# 6_channel_esp32_energy_meter.net
KiCad netlist of a schematic drawn in EAGLE
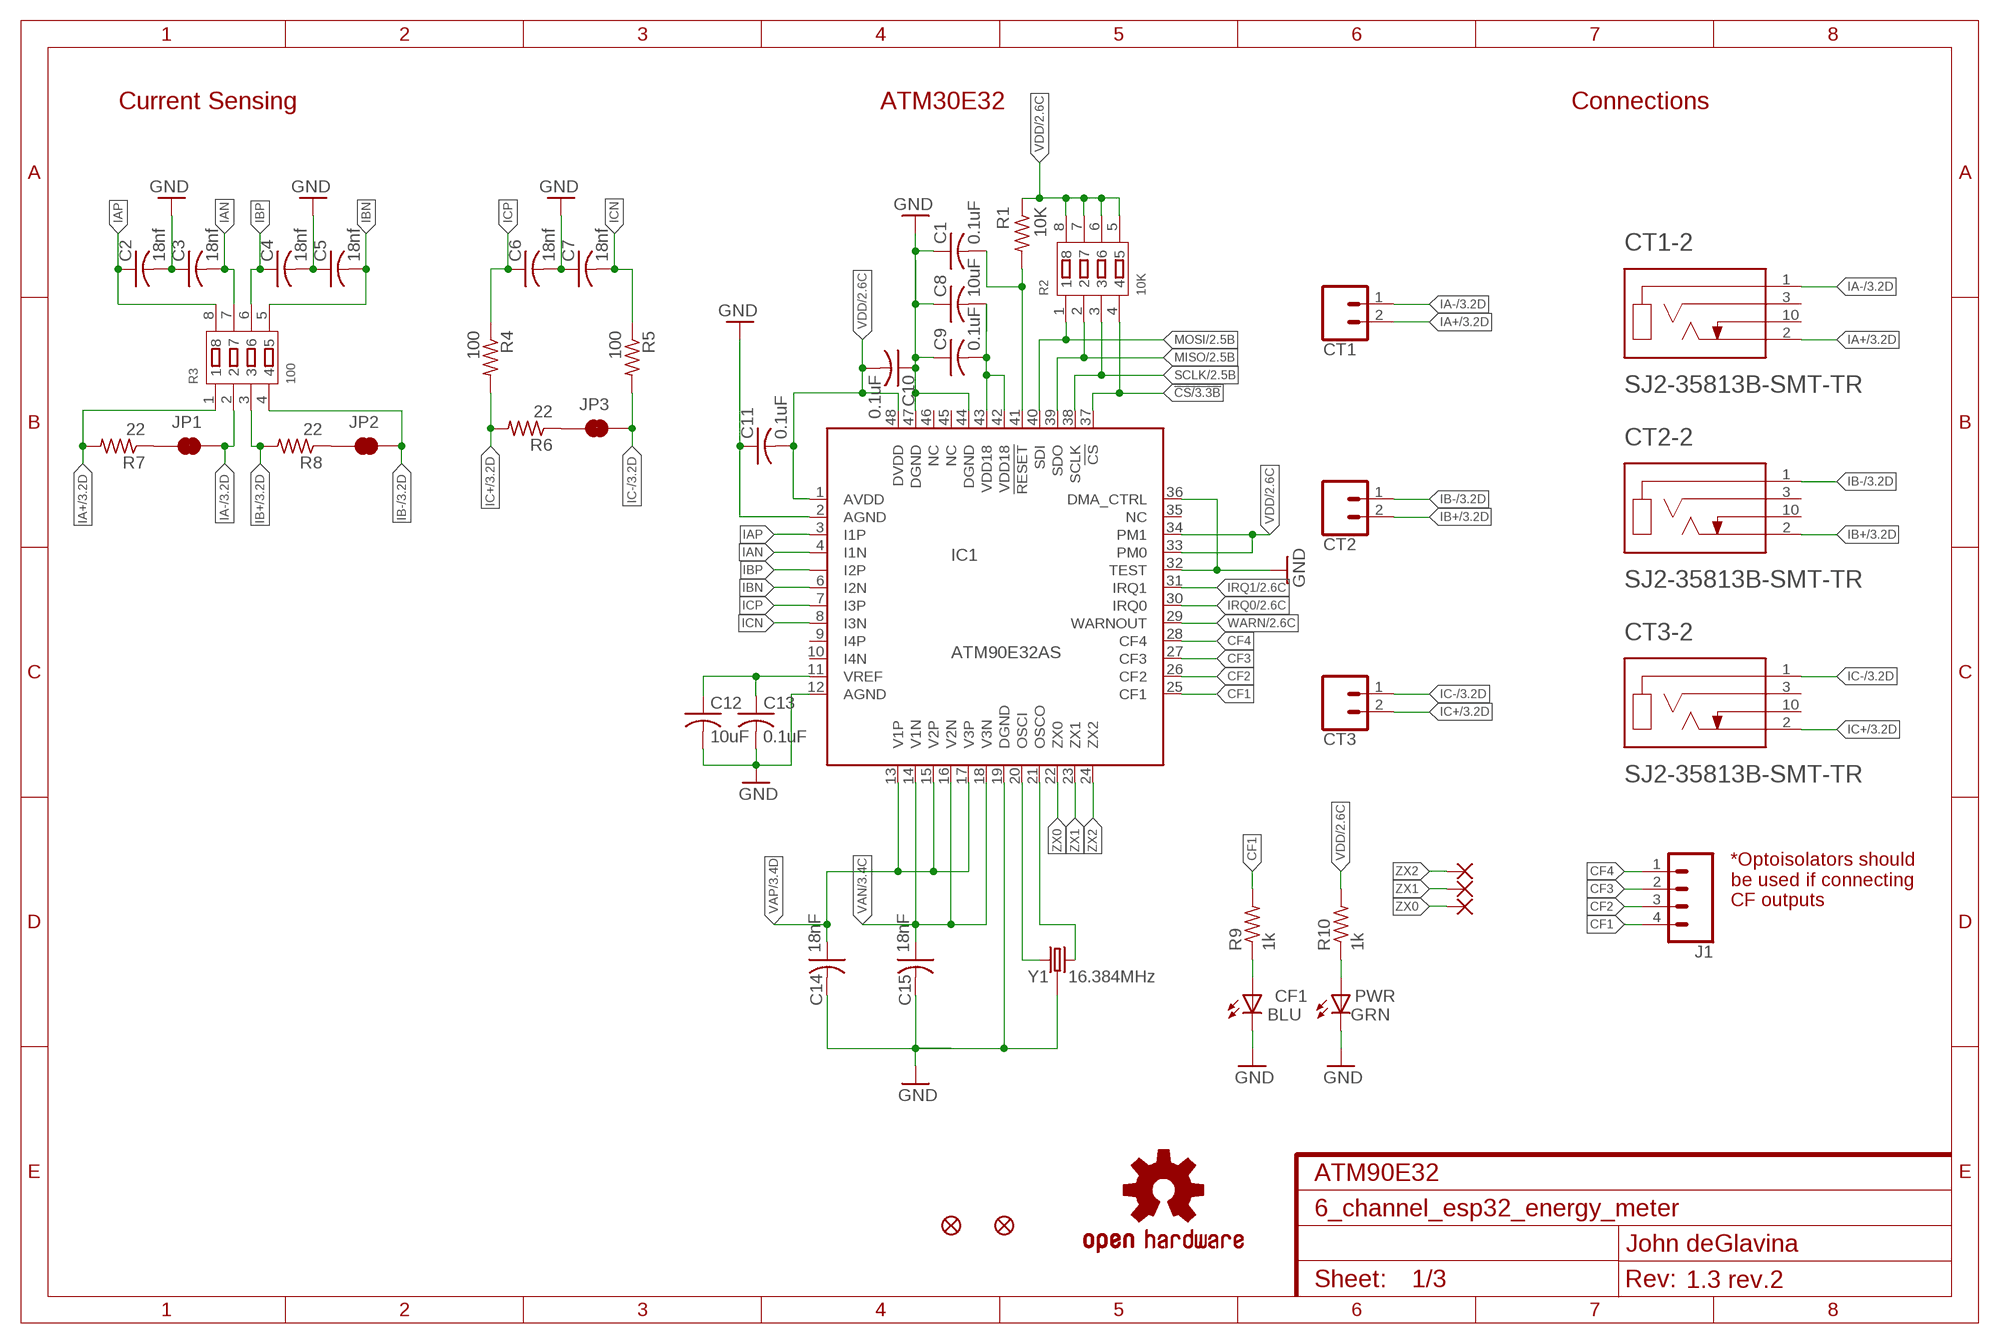
[diagram p0: schematic, sheet 1]
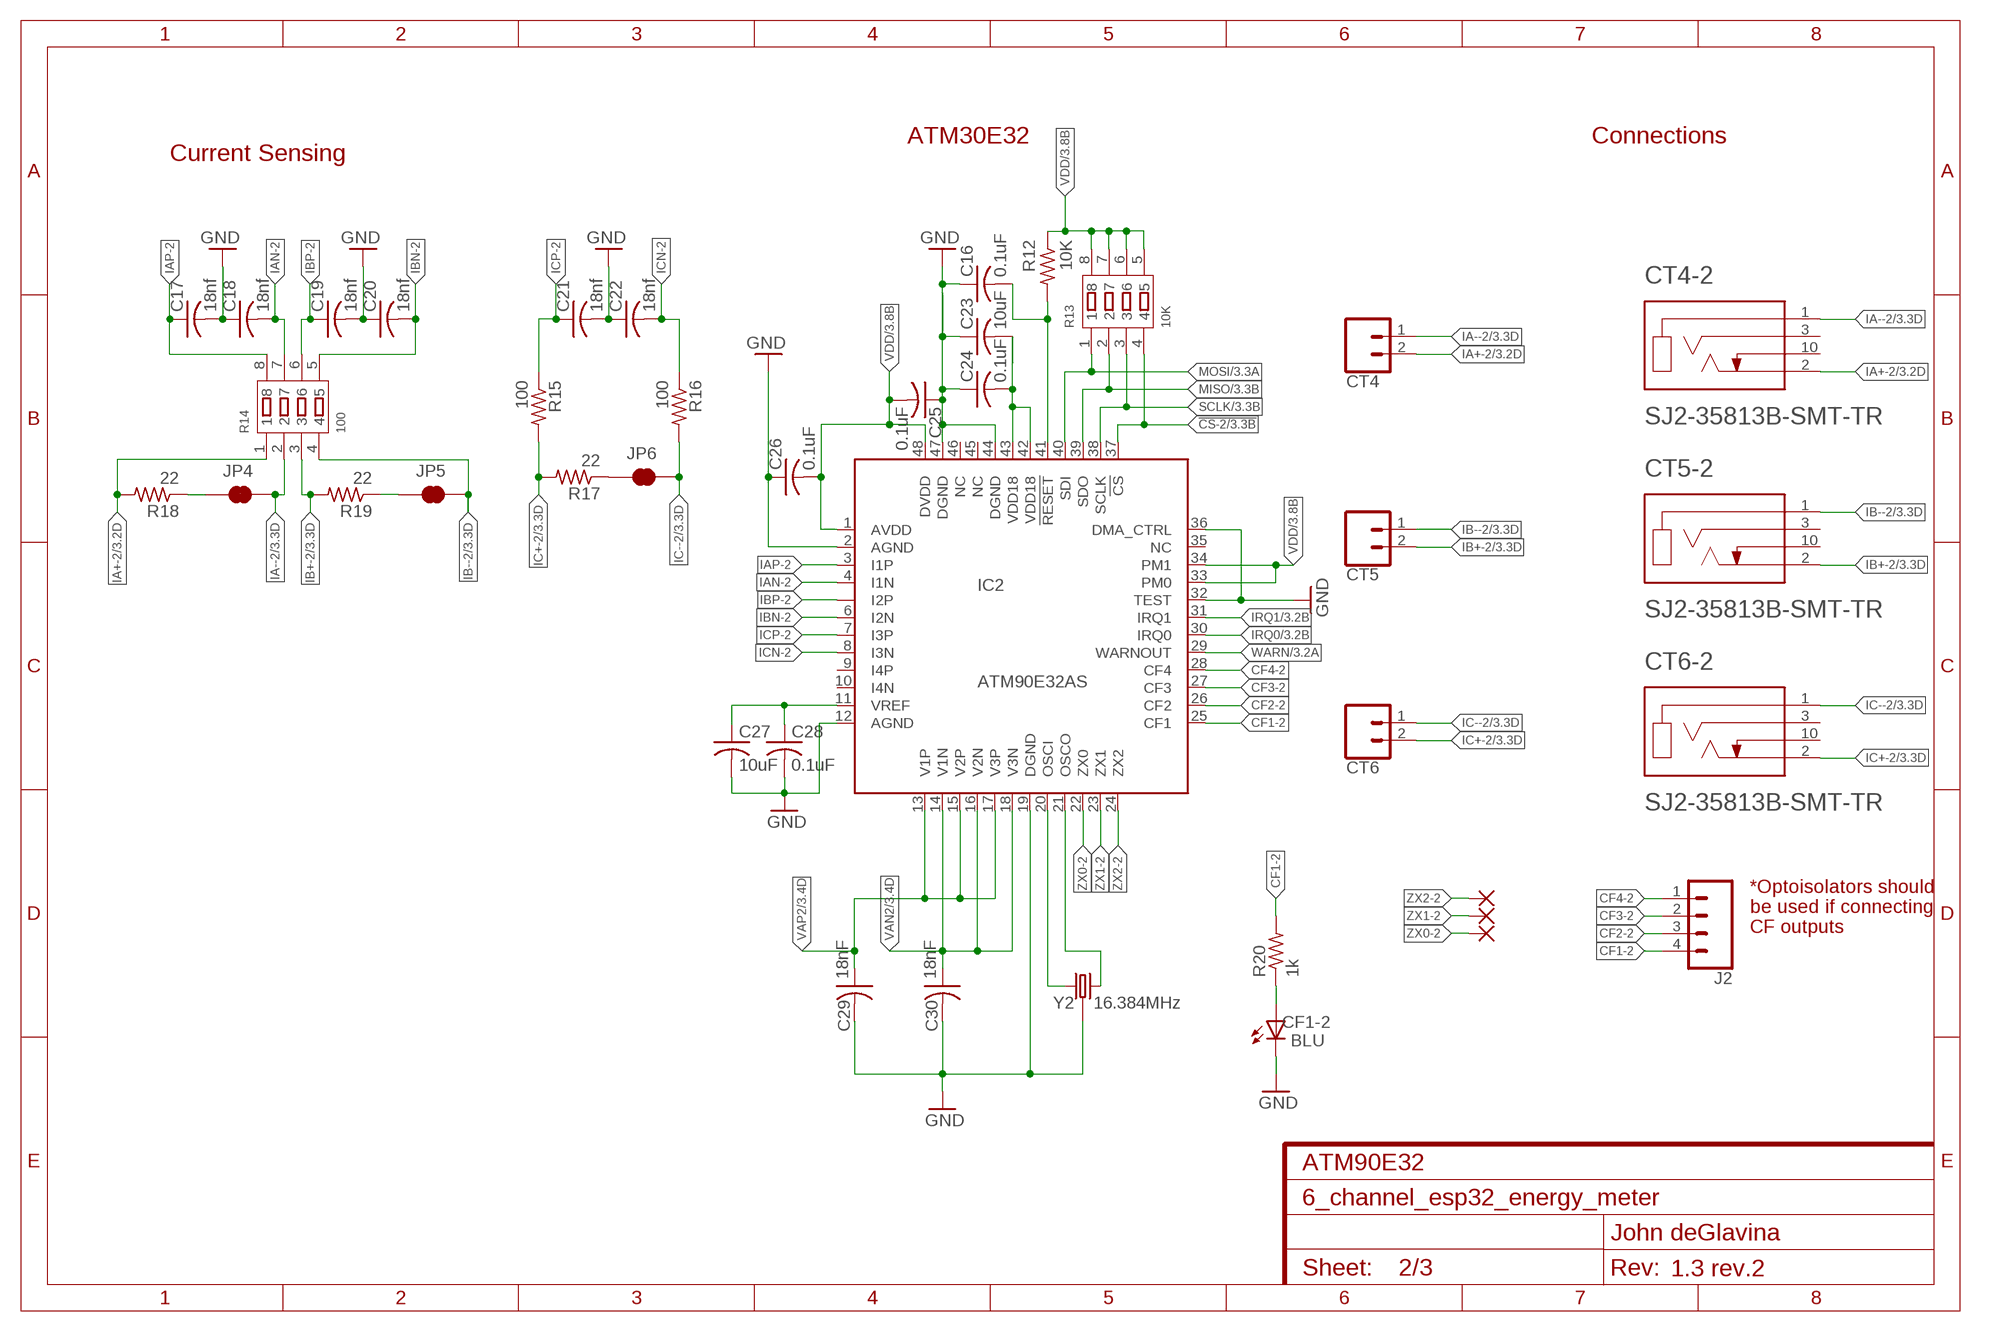
[diagram p1: schematic, sheet 2]
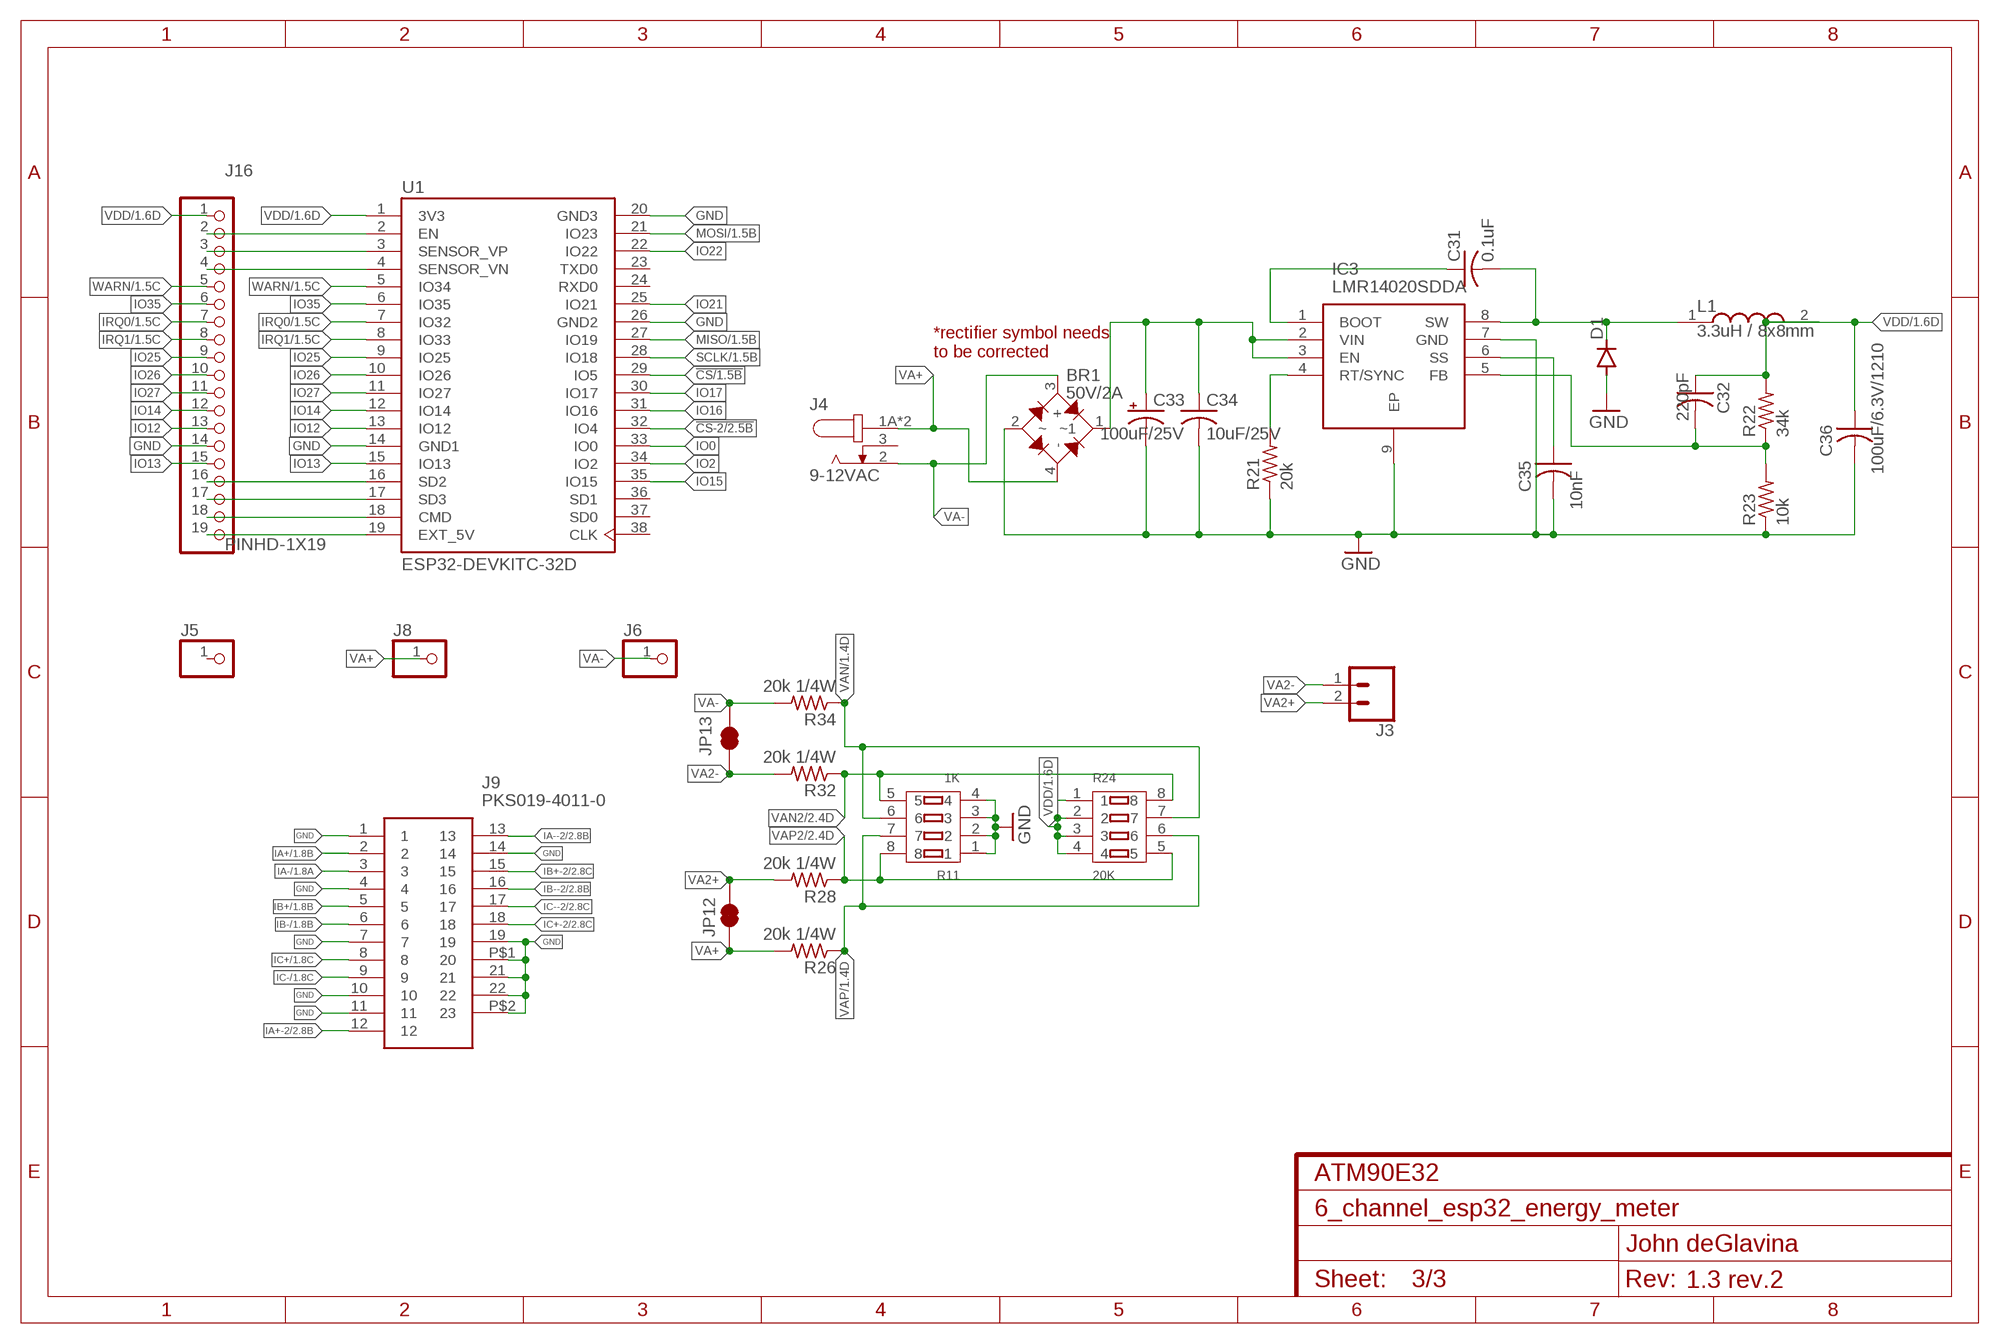
[diagram p2: schematic, sheet 3]

(export (version "E")
  (design (tool "Eeschema 10.0.6"))
  (components
    (comp (ref "BR1")
      (value "50V/2A")
      (footprint "eagle-import:SOP270P700X270-4")
      (fields
        (field (name "MANUFACTURER_PART_NUMBER") "CDBHM240L-HF")
        (field (name "MOUSER_PART_NUMBER") "750-CDBHM240L-HF")
        (field (name "RS_PART_NUMBER") "9066719")
      )
      (libsource (lib "eagle-import") (part "CDBHM240L-HF"))
    )
    (comp (ref "C31")
      (value "0.1uF")
      (footprint "eagle-import:C0603")
      (libsource (lib "eagle-import") (part "C-USC0603"))
    )
    (comp (ref "C32")
      (value "220pF")
      (footprint "eagle-import:C0603")
      (libsource (lib "eagle-import") (part "C-USC0603"))
    )
    (comp (ref "C33")
      (value "100uF/25V")
      (footprint "eagle-import:UD-6,3X7,7_NICHICON")
      (libsource (lib "eagle-import") (part "CPOL-USUD-6,3X7,7"))
    )
    (comp (ref "C34")
      (value "10uF/25V")
      (footprint "eagle-import:C0805")
      (libsource (lib "eagle-import") (part "C-USC0805"))
    )
    (comp (ref "C35")
      (value "10nF")
      (footprint "eagle-import:C0603")
      (libsource (lib "eagle-import") (part "C-USC0603"))
    )
    (comp (ref "C36")
      (value "100uF/6.3V/1210")
      (footprint "eagle-import:C1210")
      (libsource (lib "eagle-import") (part "C-USC1210"))
    )
    (comp (ref "D1")
      (value "DIODE-DO214AC")
      (footprint "eagle-import:DO214AC")
      (libsource (lib "eagle-import") (part "DIODE-DO214AC"))
    )
    (comp (ref "IC3")
      (value "LMR14020SDDA")
      (footprint "eagle-import:SOIC127P600X170-9N")
      (fields
        (field (name "MOUSER_PART_NUMBER") "595-LMR14020SDDA")
        (field (name "RS_PART_NUMBER") "1629813")
      )
      (libsource (lib "eagle-import") (part "LMR14020SDDA"))
    )
    (comp (ref "J3")
      (value "CONN_023.5MM")
      (footprint "eagle-import:SCREWTERMINAL-3.5MM-2")
      (libsource (lib "eagle-import") (part "CONN_023.5MM"))
    )
    (comp (ref "J4")
      (value "9-12VAC")
      (footprint "eagle-import:CUI_PJ-002AH-SMT-TR")
      (fields (field (name "MF") "CUI") (field (name "MP") "PJ-002AH-SMT-TR"))
      (libsource (lib "eagle-import") (part "PJ-002AH-SMT-TR"))
    )
    (comp (ref "J5")
      (value "PINHD1X1-SM1X01_SM")
      (footprint "eagle-import:1X01-SM")
      (libsource (lib "eagle-import") (part "PINHD1X1-SM1X01_SM"))
    )
    (comp (ref "J6")
      (value "PINHD1X1-SM1X01_SM")
      (footprint "eagle-import:1X01-SM")
      (libsource (lib "eagle-import") (part "PINHD1X1-SM1X01_SM"))
    )
    (comp (ref "J8")
      (value "PINHD1X1-SM1X01_SM")
      (footprint "eagle-import:1X01-SM")
      (libsource (lib "eagle-import") (part "PINHD1X1-SM1X01_SM"))
    )
    (comp (ref "J9")
      (value "PKS019-4011-0")
      (footprint "eagle-import:PKS01940110")
      (fields (field (name "MOUSER_PART_NUMBER") "945-PKS019-4011-0"))
      (libsource (lib "eagle-import") (part "PKS019-4011-0"))
    )
    (comp (ref "J16")
      (value "PINHD-1X19")
      (footprint "eagle-import:1X19")
      (fields (field (name "SPICEPREFIX") "X"))
      (libsource (lib "eagle-import") (part "PINHD-1X19"))
    )
    (comp (ref "JP12")
      (value "JUMPER-SMT_2_NC_TRACE_SILK")
      (footprint "eagle-import:SMT-JUMPER_2_NC_TRACE_SILK")
      (libsource (lib "eagle-import") (part "JUMPER-SMT_2_NC_TRACE_SILK"))
    )
    (comp (ref "JP13")
      (value "JUMPER-SMT_2_NC_TRACE_SILK")
      (footprint "eagle-import:SMT-JUMPER_2_NC_TRACE_SILK")
      (libsource (lib "eagle-import") (part "JUMPER-SMT_2_NC_TRACE_SILK"))
    )
    (comp (ref "L1")
      (value "3.3uH / 8x8mm")
      (footprint "eagle-import:INDPM8082X300N")
      (fields (field (name "MANUFACTURER_PART_NUMBER") "1273AS-H-3R3N=P3"))
      (libsource (lib "eagle-import") (part "1273AS-H-3R3N=P3"))
    )
    (comp (ref "R11")
      (value "1K")
      (footprint "eagle-import:RA1206-8")
      (fields (field (name "MPN") "Chip-Array-Series-1%"))
      (libsource (lib "eagle-import") (part "SMD-RES-ARRAY-1K-4R(RA1206-8)"))
    )
    (comp (ref "R21")
      (value "20k")
      (footprint "eagle-import:R0603")
      (libsource (lib "eagle-import") (part "R-US_R0603"))
    )
    (comp (ref "R22")
      (value "34k")
      (footprint "eagle-import:R0603")
      (libsource (lib "eagle-import") (part "R-US_R0603"))
    )
    (comp (ref "R23")
      (value "10k")
      (footprint "eagle-import:R0603")
      (libsource (lib "eagle-import") (part "R-US_R0603"))
    )
    (comp (ref "R24")
      (value "20K")
      (footprint "eagle-import:RA1206-8")
      (fields (field (name "MPN") "Chip-Array-Series-1%"))
      (libsource (lib "eagle-import") (part "SMD-RES-ARRAY-1K-4R(RA1206-8)"))
    )
    (comp (ref "R26")
      (value "20k 1/4W")
      (footprint "eagle-import:R0603")
      (libsource (lib "eagle-import") (part "R-US_R0603"))
    )
    (comp (ref "R28")
      (value "20k 1/4W")
      (footprint "eagle-import:R0603")
      (libsource (lib "eagle-import") (part "R-US_R0603"))
    )
    (comp (ref "R32")
      (value "20k 1/4W")
      (footprint "eagle-import:R0603")
      (libsource (lib "eagle-import") (part "R-US_R0603"))
    )
    (comp (ref "R34")
      (value "20k 1/4W")
      (footprint "eagle-import:R0603")
      (libsource (lib "eagle-import") (part "R-US_R0603"))
    )
    (comp (ref "U1")
      (value "ESP32-DEVKITC-32D")
      (footprint "eagle-import:MODULE_ESP32-DEVKITC-32D")
      (fields (field (name "MF") "Espressif Systems"))
      (libsource (lib "eagle-import") (part "ESP32-DEVKITC-32D"))
    )
    (comp (ref "C16")
      (value "0.1uF")
      (footprint "eagle-import:C0603")
      (libsource (lib "eagle-import") (part "C-USC0603"))
    )
    (comp (ref "C17")
      (value "18nf")
      (footprint "eagle-import:C0603")
      (libsource (lib "eagle-import") (part "C-USC0603"))
    )
    (comp (ref "C18")
      (value "18nf")
      (footprint "eagle-import:C0603")
      (libsource (lib "eagle-import") (part "C-USC0603"))
    )
    (comp (ref "C19")
      (value "18nf")
      (footprint "eagle-import:C0603")
      (libsource (lib "eagle-import") (part "C-USC0603"))
    )
    (comp (ref "C20")
      (value "18nf")
      (footprint "eagle-import:C0603")
      (libsource (lib "eagle-import") (part "C-USC0603"))
    )
    (comp (ref "C21")
      (value "18nf")
      (footprint "eagle-import:C0603")
      (libsource (lib "eagle-import") (part "C-USC0603"))
    )
    (comp (ref "C22")
      (value "18nf")
      (footprint "eagle-import:C0603")
      (libsource (lib "eagle-import") (part "C-USC0603"))
    )
    (comp (ref "C23")
      (value "10uF")
      (footprint "eagle-import:C0603")
      (libsource (lib "eagle-import") (part "C-USC0603"))
    )
    (comp (ref "C24")
      (value "0.1uF")
      (footprint "eagle-import:C0603")
      (libsource (lib "eagle-import") (part "C-USC0603"))
    )
    (comp (ref "C25")
      (value "0.1uF")
      (footprint "eagle-import:C0603")
      (libsource (lib "eagle-import") (part "C-USC0603"))
    )
    (comp (ref "C26")
      (value "0.1uF")
      (footprint "eagle-import:C0603")
      (libsource (lib "eagle-import") (part "C-USC0603"))
    )
    (comp (ref "C27")
      (value "10uF")
      (footprint "eagle-import:C0603")
      (libsource (lib "eagle-import") (part "C-USC0603"))
    )
    (comp (ref "C28")
      (value "0.1uF")
      (footprint "eagle-import:C0603")
      (libsource (lib "eagle-import") (part "C-USC0603"))
    )
    (comp (ref "C29")
      (value "18nF")
      (footprint "eagle-import:C0603")
      (libsource (lib "eagle-import") (part "C-USC0603"))
    )
    (comp (ref "C30")
      (value "18nF")
      (footprint "eagle-import:C0603")
      (libsource (lib "eagle-import") (part "C-USC0603"))
    )
    (comp (ref "CF1-2")
      (value "BLU")
      (footprint "eagle-import:CHIPLED_0603")
      (libsource (lib "eagle-import") (part "LEDCHIPLED_0603"))
    )
    (comp (ref "CT4")
      (value "CONN_023.5MM")
      (footprint "eagle-import:SCREWTERMINAL-3.5MM-2")
      (libsource (lib "eagle-import") (part "SparkFun-Connectors_8231346_CONN_023.5MM"))
    )
    (comp (ref "CT4-2")
      (value "SJ2-35813B-SMT-TR")
      (footprint "eagle-import:CUI_SJ2-35813B-SMT-TR")
      (fields (field (name "MANUFACTURER") "CUI"))
      (libsource (lib "eagle-import") (part "SJ2-35813B-SMT-TR"))
    )
    (comp (ref "CT5")
      (value "CONN_023.5MM")
      (footprint "eagle-import:SCREWTERMINAL-3.5MM-2")
      (libsource (lib "eagle-import") (part "SparkFun-Connectors_8231346_CONN_023.5MM"))
    )
    (comp (ref "CT5-2")
      (value "SJ2-35813B-SMT-TR")
      (footprint "eagle-import:CUI_SJ2-35813B-SMT-TR")
      (fields (field (name "MANUFACTURER") "CUI"))
      (libsource (lib "eagle-import") (part "SJ2-35813B-SMT-TR"))
    )
    (comp (ref "CT6")
      (value "CONN_023.5MM")
      (footprint "eagle-import:SCREWTERMINAL-3.5MM-2")
      (libsource (lib "eagle-import") (part "SparkFun-Connectors_8231346_CONN_023.5MM"))
    )
    (comp (ref "CT6-2")
      (value "SJ2-35813B-SMT-TR")
      (footprint "eagle-import:CUI_SJ2-35813B-SMT-TR")
      (fields (field (name "MANUFACTURER") "CUI"))
      (libsource (lib "eagle-import") (part "SJ2-35813B-SMT-TR"))
    )
    (comp (ref "IC2")
      (value "ATM90E32AS")
      (footprint "eagle-import:QFP50P900X900X120-48")
      (fields (field (name "SPICEPREFIX") "X"))
      (libsource (lib "eagle-import") (part "ATM90E36"))
    )
    (comp (ref "J2")
      (value "CONN_04")
      (footprint "eagle-import:1X04")
      (libsource (lib "eagle-import") (part "CONN_04"))
    )
    (comp (ref "JP4")
      (value "JUMPER-SMT_2_NC_TRACE_SILK")
      (footprint "eagle-import:SMT-JUMPER_2_NC_TRACE_SILK")
      (libsource (lib "eagle-import") (part "JUMPER-SMT_2_NC_TRACE_SILK"))
    )
    (comp (ref "JP5")
      (value "JUMPER-SMT_2_NC_TRACE_SILK")
      (footprint "eagle-import:SMT-JUMPER_2_NC_TRACE_SILK")
      (libsource (lib "eagle-import") (part "JUMPER-SMT_2_NC_TRACE_SILK"))
    )
    (comp (ref "JP6")
      (value "JUMPER-SMT_2_NC_TRACE_SILK")
      (footprint "eagle-import:SMT-JUMPER_2_NC_TRACE_SILK")
      (libsource (lib "eagle-import") (part "JUMPER-SMT_2_NC_TRACE_SILK"))
    )
    (comp (ref "R12")
      (value "10K")
      (footprint "eagle-import:R0603")
      (libsource (lib "eagle-import") (part "R-US_R0603"))
    )
    (comp (ref "R13")
      (value "10K")
      (footprint "eagle-import:RA1206-8")
      (fields (field (name "MPN") "Chip-Array-Series-1%"))
      (libsource (lib "eagle-import") (part "SMD-RES-ARRAY-1K-4R(RA1206-8)"))
    )
    (comp (ref "R14")
      (value "100")
      (footprint "eagle-import:RA1206-8")
      (fields (field (name "MPN") "Chip-Array-Series-1%"))
      (libsource (lib "eagle-import") (part "SMD-RES-ARRAY-1K-4R(RA1206-8)"))
    )
    (comp (ref "R15")
      (value "100")
      (footprint "eagle-import:R0603")
      (libsource (lib "eagle-import") (part "R-US_R0603"))
    )
    (comp (ref "R16")
      (value "100")
      (footprint "eagle-import:R0603")
      (libsource (lib "eagle-import") (part "R-US_R0603"))
    )
    (comp (ref "R17")
      (value "22")
      (footprint "eagle-import:R0603")
      (libsource (lib "eagle-import") (part "R-US_R0603"))
    )
    (comp (ref "R18")
      (value "22")
      (footprint "eagle-import:R0603")
      (libsource (lib "eagle-import") (part "R-US_R0603"))
    )
    (comp (ref "R19")
      (value "22")
      (footprint "eagle-import:R0603")
      (libsource (lib "eagle-import") (part "R-US_R0603"))
    )
    (comp (ref "R20")
      (value "1k")
      (footprint "eagle-import:R0603")
      (libsource (lib "eagle-import") (part "R-US_R0603"))
    )
    (comp (ref "Y2")
      (value "16.384MHz")
      (footprint "eagle-import:CRYSTAL-SMD-3.2X2.5MM")
      (libsource (lib "eagle-import") (part "CRYSTAL-GROUNDEDSMD-3.2X2.5"))
    )
    (comp (ref "ZX0-2")
      (value "WIREPADSMD1,27-254")
      (footprint "eagle-import:SMD1,27-2,54")
      (libsource (lib "eagle-import") (part "WIREPADSMD1,27-254"))
    )
    (comp (ref "ZX1-2")
      (value "WIREPADSMD1,27-254")
      (footprint "eagle-import:SMD1,27-2,54")
      (libsource (lib "eagle-import") (part "WIREPADSMD1,27-254"))
    )
    (comp (ref "ZX2-2")
      (value "WIREPADSMD1,27-254")
      (footprint "eagle-import:SMD1,27-2,54")
      (libsource (lib "eagle-import") (part "WIREPADSMD1,27-254"))
    )
    (comp (ref "C1")
      (value "0.1uF")
      (footprint "eagle-import:C0603")
      (libsource (lib "eagle-import") (part "C-USC0603"))
    )
    (comp (ref "C2")
      (value "18nf")
      (footprint "eagle-import:C0603")
      (libsource (lib "eagle-import") (part "C-USC0603"))
    )
    (comp (ref "C3")
      (value "18nf")
      (footprint "eagle-import:C0603")
      (libsource (lib "eagle-import") (part "C-USC0603"))
    )
    (comp (ref "C4")
      (value "18nf")
      (footprint "eagle-import:C0603")
      (libsource (lib "eagle-import") (part "C-USC0603"))
    )
    (comp (ref "C5")
      (value "18nf")
      (footprint "eagle-import:C0603")
      (libsource (lib "eagle-import") (part "C-USC0603"))
    )
    (comp (ref "C6")
      (value "18nf")
      (footprint "eagle-import:C0603")
      (libsource (lib "eagle-import") (part "C-USC0603"))
    )
    (comp (ref "C7")
      (value "18nf")
      (footprint "eagle-import:C0603")
      (libsource (lib "eagle-import") (part "C-USC0603"))
    )
    (comp (ref "C8")
      (value "10uF")
      (footprint "eagle-import:C0603")
      (libsource (lib "eagle-import") (part "C-USC0603"))
    )
    (comp (ref "C9")
      (value "0.1uF")
      (footprint "eagle-import:C0603")
      (libsource (lib "eagle-import") (part "C-USC0603"))
    )
    (comp (ref "C10")
      (value "0.1uF")
      (footprint "eagle-import:C0603")
      (libsource (lib "eagle-import") (part "C-USC0603"))
    )
    (comp (ref "C11")
      (value "0.1uF")
      (footprint "eagle-import:C0603")
      (libsource (lib "eagle-import") (part "C-USC0603"))
    )
    (comp (ref "C12")
      (value "10uF")
      (footprint "eagle-import:C0603")
      (libsource (lib "eagle-import") (part "C-USC0603"))
    )
    (comp (ref "C13")
      (value "0.1uF")
      (footprint "eagle-import:C0603")
      (libsource (lib "eagle-import") (part "C-USC0603"))
    )
    (comp (ref "C14")
      (value "18nF")
      (footprint "eagle-import:C0603")
      (libsource (lib "eagle-import") (part "C-USC0603"))
    )
    (comp (ref "C15")
      (value "18nF")
      (footprint "eagle-import:C0603")
      (libsource (lib "eagle-import") (part "C-USC0603"))
    )
    (comp (ref "CF1")
      (value "BLU")
      (footprint "eagle-import:CHIPLED_0603")
      (libsource (lib "eagle-import") (part "LEDCHIPLED_0603"))
    )
    (comp (ref "CT1")
      (value "CONN_023.5MM")
      (footprint "eagle-import:SCREWTERMINAL-3.5MM-2")
      (libsource (lib "eagle-import") (part "SparkFun-Connectors_8231346_CONN_023.5MM"))
    )
    (comp (ref "CT1-2")
      (value "SJ2-35813B-SMT-TR")
      (footprint "eagle-import:CUI_SJ2-35813B-SMT-TR")
      (fields (field (name "MANUFACTURER") "CUI"))
      (libsource (lib "eagle-import") (part "SJ2-35813B-SMT-TR"))
    )
    (comp (ref "CT2")
      (value "CONN_023.5MM")
      (footprint "eagle-import:SCREWTERMINAL-3.5MM-2")
      (libsource (lib "eagle-import") (part "SparkFun-Connectors_8231346_CONN_023.5MM"))
    )
    (comp (ref "CT2-2")
      (value "SJ2-35813B-SMT-TR")
      (footprint "eagle-import:CUI_SJ2-35813B-SMT-TR")
      (fields (field (name "MANUFACTURER") "CUI"))
      (libsource (lib "eagle-import") (part "SJ2-35813B-SMT-TR"))
    )
    (comp (ref "CT3")
      (value "CONN_023.5MM")
      (footprint "eagle-import:SCREWTERMINAL-3.5MM-2")
      (libsource (lib "eagle-import") (part "SparkFun-Connectors_8231346_CONN_023.5MM"))
    )
    (comp (ref "CT3-2")
      (value "SJ2-35813B-SMT-TR")
      (footprint "eagle-import:CUI_SJ2-35813B-SMT-TR")
      (fields (field (name "MANUFACTURER") "CUI"))
      (libsource (lib "eagle-import") (part "SJ2-35813B-SMT-TR"))
    )
    (comp (ref "FD1")
      (value "FIDUCIALUFIDUCIAL")
      (footprint "eagle-import:FIDUCIAL-MICRO")
      (libsource (lib "eagle-import") (part "FIDUCIALUFIDUCIAL"))
    )
    (comp (ref "FD2")
      (value "FIDUCIALUFIDUCIAL")
      (footprint "eagle-import:FIDUCIAL-MICRO")
      (libsource (lib "eagle-import") (part "FIDUCIALUFIDUCIAL"))
    )
    (comp (ref "IC1")
      (value "ATM90E32AS")
      (footprint "eagle-import:QFP50P900X900X120-48")
      (fields (field (name "SPICEPREFIX") "X"))
      (libsource (lib "eagle-import") (part "ATM90E36"))
    )
    (comp (ref "J1")
      (value "CONN_04")
      (footprint "eagle-import:1X04")
      (libsource (lib "eagle-import") (part "CONN_04"))
    )
    (comp (ref "JP1")
      (value "JUMPER-SMT_2_NC_TRACE_SILK")
      (footprint "eagle-import:SMT-JUMPER_2_NC_TRACE_SILK")
      (libsource (lib "eagle-import") (part "JUMPER-SMT_2_NC_TRACE_SILK"))
    )
    (comp (ref "JP2")
      (value "JUMPER-SMT_2_NC_TRACE_SILK")
      (footprint "eagle-import:SMT-JUMPER_2_NC_TRACE_SILK")
      (libsource (lib "eagle-import") (part "JUMPER-SMT_2_NC_TRACE_SILK"))
    )
    (comp (ref "JP3")
      (value "JUMPER-SMT_2_NC_TRACE_SILK")
      (footprint "eagle-import:SMT-JUMPER_2_NC_TRACE_SILK")
      (libsource (lib "eagle-import") (part "JUMPER-SMT_2_NC_TRACE_SILK"))
    )
    (comp (ref "LOGO1")
      (value "OSHW-LOGOS")
      (footprint "eagle-import:OSHW-LOGO-S")
      (libsource (lib "eagle-import") (part "OSHW-LOGOS"))
    )
    (comp (ref "PWR")
      (value "GRN")
      (footprint "eagle-import:CHIPLED_0603")
      (libsource (lib "eagle-import") (part "LEDCHIPLED_0603"))
    )
    (comp (ref "R1")
      (value "10K")
      (footprint "eagle-import:R0603")
      (libsource (lib "eagle-import") (part "R-US_R0603"))
    )
    (comp (ref "R2")
      (value "10K")
      (footprint "eagle-import:RA1206-8")
      (fields (field (name "MPN") "Chip-Array-Series-1%"))
      (libsource (lib "eagle-import") (part "SMD-RES-ARRAY-1K-4R(RA1206-8)"))
    )
    (comp (ref "R3")
      (value "100")
      (footprint "eagle-import:RA1206-8")
      (fields (field (name "MPN") "Chip-Array-Series-1%"))
      (libsource (lib "eagle-import") (part "SMD-RES-ARRAY-1K-4R(RA1206-8)"))
    )
    (comp (ref "R4")
      (value "100")
      (footprint "eagle-import:R0603")
      (libsource (lib "eagle-import") (part "R-US_R0603"))
    )
    (comp (ref "R5")
      (value "100")
      (footprint "eagle-import:R0603")
      (libsource (lib "eagle-import") (part "R-US_R0603"))
    )
    (comp (ref "R6")
      (value "22")
      (footprint "eagle-import:R0603")
      (libsource (lib "eagle-import") (part "R-US_R0603"))
    )
    (comp (ref "R7")
      (value "22")
      (footprint "eagle-import:R0603")
      (libsource (lib "eagle-import") (part "R-US_R0603"))
    )
    (comp (ref "R8")
      (value "22")
      (footprint "eagle-import:R0603")
      (libsource (lib "eagle-import") (part "R-US_R0603"))
    )
    (comp (ref "R9")
      (value "1k")
      (footprint "eagle-import:R0603")
      (libsource (lib "eagle-import") (part "R-US_R0603"))
    )
    (comp (ref "R10")
      (value "1k")
      (footprint "eagle-import:R0603")
      (libsource (lib "eagle-import") (part "R-US_R0603"))
    )
    (comp (ref "Y1")
      (value "16.384MHz")
      (footprint "eagle-import:CRYSTAL-SMD-3.2X2.5MM")
      (libsource (lib "eagle-import") (part "CRYSTAL-GROUNDEDSMD-3.2X2.5"))
    )
    (comp (ref "ZX0")
      (value "WIREPADSMD1,27-254")
      (footprint "eagle-import:SMD1,27-2,54")
      (libsource (lib "eagle-import") (part "WIREPADSMD1,27-254"))
    )
    (comp (ref "ZX1")
      (value "WIREPADSMD1,27-254")
      (footprint "eagle-import:SMD1,27-2,54")
      (libsource (lib "eagle-import") (part "WIREPADSMD1,27-254"))
    )
    (comp (ref "ZX2")
      (value "WIREPADSMD1,27-254")
      (footprint "eagle-import:SMD1,27-2,54")
      (libsource (lib "eagle-import") (part "WIREPADSMD1,27-254"))
    )
  )
  (nets
    (net (code "1") (name "CF1") (class "Default")
      (node (ref "IC1") (pin "25") (pinfunction "CF1_25") (pintype "output"))
      (node (ref "J1") (pin "4") (pinfunction "4_4") (pintype "passive"))
      (node (ref "R9") (pin "2") (pinfunction "2_2") (pintype "passive"))
    )
    (net (code "2") (name "CF1-2") (class "Default")
      (node (ref "IC2") (pin "25") (pinfunction "CF1_25") (pintype "output"))
      (node (ref "J2") (pin "4") (pinfunction "4_4") (pintype "passive"))
      (node (ref "R20") (pin "2") (pinfunction "2_2") (pintype "passive"))
    )
    (net (code "3") (name "CF2") (class "Default")
      (node (ref "IC1") (pin "26") (pinfunction "CF2_26") (pintype "output"))
      (node (ref "J1") (pin "3") (pinfunction "3_3") (pintype "passive"))
    )
    (net (code "4") (name "CF2-2") (class "Default")
      (node (ref "IC2") (pin "26") (pinfunction "CF2_26") (pintype "output"))
      (node (ref "J2") (pin "3") (pinfunction "3_3") (pintype "passive"))
    )
    (net (code "5") (name "CF3") (class "Default")
      (node (ref "IC1") (pin "27") (pinfunction "CF3_27") (pintype "output"))
      (node (ref "J1") (pin "2") (pinfunction "2_2") (pintype "passive"))
    )
    (net (code "6") (name "CF3-2") (class "Default")
      (node (ref "IC2") (pin "27") (pinfunction "CF3_27") (pintype "output"))
      (node (ref "J2") (pin "2") (pinfunction "2_2") (pintype "passive"))
    )
    (net (code "7") (name "CF4") (class "Default")
      (node (ref "IC1") (pin "28") (pinfunction "CF4_28") (pintype "output"))
      (node (ref "J1") (pin "1") (pinfunction "1_1") (pintype "passive"))
    )
    (net (code "8") (name "CF4-2") (class "Default")
      (node (ref "IC2") (pin "28") (pinfunction "CF4_28") (pintype "output"))
      (node (ref "J2") (pin "1") (pinfunction "1_1") (pintype "passive"))
    )
    (net (code "9") (name "GND") (class "Default")
      (node (ref "BR1") (pin "2") (pinfunction "~_2") (pintype "bidirectional"))
      (node (ref "C1") (pin "1") (pinfunction "1_1") (pintype "passive"))
      (node (ref "C10") (pin "1") (pinfunction "1_1") (pintype "passive"))
      (node (ref "C11") (pin "1") (pinfunction "1_1") (pintype "passive"))
      (node (ref "C12") (pin "2") (pinfunction "2_2") (pintype "passive"))
      (node (ref "C13") (pin "2") (pinfunction "2_2") (pintype "passive"))
      (node (ref "C14") (pin "2") (pinfunction "2_2") (pintype "passive"))
      (node (ref "C15") (pin "2") (pinfunction "2_2") (pintype "passive"))
      (node (ref "C16") (pin "1") (pinfunction "1_1") (pintype "passive"))
      (node (ref "C17") (pin "2") (pinfunction "2_2") (pintype "passive"))
      (node (ref "C18") (pin "1") (pinfunction "1_1") (pintype "passive"))
      (node (ref "C19") (pin "2") (pinfunction "2_2") (pintype "passive"))
      (node (ref "C2") (pin "2") (pinfunction "2_2") (pintype "passive"))
      (node (ref "C20") (pin "1") (pinfunction "1_1") (pintype "passive"))
      (node (ref "C21") (pin "2") (pinfunction "2_2") (pintype "passive"))
      (node (ref "C22") (pin "1") (pinfunction "1_1") (pintype "passive"))
      (node (ref "C23") (pin "1") (pinfunction "1_1") (pintype "passive"))
      (node (ref "C24") (pin "1") (pinfunction "1_1") (pintype "passive"))
      (node (ref "C25") (pin "1") (pinfunction "1_1") (pintype "passive"))
      (node (ref "C26") (pin "1") (pinfunction "1_1") (pintype "passive"))
      (node (ref "C27") (pin "2") (pinfunction "2_2") (pintype "passive"))
      (node (ref "C28") (pin "2") (pinfunction "2_2") (pintype "passive"))
      (node (ref "C29") (pin "2") (pinfunction "2_2") (pintype "passive"))
      (node (ref "C3") (pin "1") (pinfunction "1_1") (pintype "passive"))
      (node (ref "C30") (pin "2") (pinfunction "2_2") (pintype "passive"))
      (node (ref "C33") (pin "-") (pinfunction "-_-") (pintype "passive"))
      (node (ref "C34") (pin "2") (pinfunction "2_2") (pintype "passive"))
      (node (ref "C35") (pin "2") (pinfunction "2_2") (pintype "passive"))
      (node (ref "C36") (pin "2") (pinfunction "2_2") (pintype "passive"))
      (node (ref "C4") (pin "2") (pinfunction "2_2") (pintype "passive"))
      (node (ref "C5") (pin "1") (pinfunction "1_1") (pintype "passive"))
      (node (ref "C6") (pin "2") (pinfunction "2_2") (pintype "passive"))
      (node (ref "C7") (pin "1") (pinfunction "1_1") (pintype "passive"))
      (node (ref "C8") (pin "1") (pinfunction "1_1") (pintype "passive"))
      (node (ref "C9") (pin "1") (pinfunction "1_1") (pintype "passive"))
      (node (ref "CF1") (pin "C") (pinfunction "C_C") (pintype "passive"))
      (node (ref "CF1-2") (pin "C") (pinfunction "C_C") (pintype "passive"))
      (node (ref "D1") (pin "A") (pinfunction "A_A") (pintype "passive"))
      (node (ref "IC1") (pin "12") (pinfunction "AGND_12") (pintype "power_in"))
      (node (ref "IC1") (pin "19") (pinfunction "DGND_19") (pintype "power_in"))
      (node (ref "IC1") (pin "2") (pinfunction "AGND_2") (pintype "power_in"))
      (node (ref "IC1") (pin "32") (pinfunction "TEST_32") (pintype "power_in"))
      (node (ref "IC1") (pin "36") (pinfunction "DMA_CTRL_36") (pintype "input"))
      (node (ref "IC1") (pin "44") (pinfunction "DGND_44") (pintype "power_in"))
      (node (ref "IC1") (pin "47") (pinfunction "DGND_47") (pintype "power_in"))
      (node (ref "IC2") (pin "12") (pinfunction "AGND_12") (pintype "power_in"))
      (node (ref "IC2") (pin "19") (pinfunction "DGND_19") (pintype "power_in"))
      (node (ref "IC2") (pin "2") (pinfunction "AGND_2") (pintype "power_in"))
      (node (ref "IC2") (pin "32") (pinfunction "TEST_32") (pintype "power_in"))
      (node (ref "IC2") (pin "36") (pinfunction "DMA_CTRL_36") (pintype "input"))
      (node (ref "IC2") (pin "44") (pinfunction "DGND_44") (pintype "power_in"))
      (node (ref "IC2") (pin "47") (pinfunction "DGND_47") (pintype "power_in"))
      (node (ref "IC3") (pin "7") (pinfunction "GND_7") (pintype "power_in"))
      (node (ref "IC3") (pin "9") (pinfunction "EP_9") (pintype "power_in"))
      (node (ref "J16") (pin "14") (pinfunction "14_14") (pintype "passive"))
      (node (ref "J9") (pin "1") (pinfunction "1_1") (pintype "bidirectional"))
      (node (ref "J9") (pin "10") (pinfunction "10_10") (pintype "bidirectional"))
      (node (ref "J9") (pin "11") (pinfunction "11_11") (pintype "bidirectional"))
      (node (ref "J9") (pin "14") (pinfunction "14_14") (pintype "bidirectional"))
      (node (ref "J9") (pin "19") (pinfunction "19_19") (pintype "bidirectional"))
      (node (ref "J9") (pin "21") (pinfunction "21_21") (pintype "bidirectional"))
      (node (ref "J9") (pin "22") (pinfunction "22_22") (pintype "bidirectional"))
      (node (ref "J9") (pin "4") (pinfunction "4_4") (pintype "bidirectional"))
      (node (ref "J9") (pin "7") (pinfunction "7_7") (pintype "bidirectional"))
      (node (ref "J9") (pin "P$1") (pinfunction "20_P$1") (pintype "bidirectional"))
      (node (ref "J9") (pin "P$2") (pinfunction "23_P$2") (pintype "bidirectional"))
      (node (ref "PWR") (pin "C") (pinfunction "C_C") (pintype "passive"))
      (node (ref "R11") (pin "1") (pinfunction "1_1") (pintype "bidirectional"))
      (node (ref "R11") (pin "2") (pinfunction "2_2") (pintype "bidirectional"))
      (node (ref "R11") (pin "3") (pinfunction "3_3") (pintype "bidirectional"))
      (node (ref "R11") (pin "4") (pinfunction "4_4") (pintype "bidirectional"))
      (node (ref "R21") (pin "1") (pinfunction "1_1") (pintype "passive"))
      (node (ref "R23") (pin "1") (pinfunction "1_1") (pintype "passive"))
      (node (ref "U1") (pin "14") (pinfunction "GND1_14") (pintype "power_in"))
      (node (ref "U1") (pin "20") (pinfunction "GND3_20") (pintype "power_in"))
      (node (ref "U1") (pin "26") (pinfunction "GND2_26") (pintype "power_in"))
      (node (ref "Y1") (pin "2") (pinfunction "3_2") (pintype "passive"))
      (node (ref "Y1") (pin "4") (pinfunction "3_4") (pintype "passive"))
      (node (ref "Y2") (pin "2") (pinfunction "3_2") (pintype "passive"))
      (node (ref "Y2") (pin "4") (pinfunction "3_4") (pintype "passive"))
    )
    (net (code "10") (name "IA+") (class "Default")
      (node (ref "CT1") (pin "2") (pinfunction "2_2") (pintype "passive"))
      (node (ref "CT1-2") (pin "2") (pinfunction "TIP_2") (pintype "passive"))
      (node (ref "J9") (pin "2") (pinfunction "2_2") (pintype "bidirectional"))
      (node (ref "R3") (pin "1") (pinfunction "1_1") (pintype "bidirectional"))
      (node (ref "R7") (pin "2") (pinfunction "2_2") (pintype "passive"))
    )
    (net (code "11") (name "IA+-2") (class "Default")
      (node (ref "CT4") (pin "2") (pinfunction "2_2") (pintype "passive"))
      (node (ref "CT4-2") (pin "2") (pinfunction "TIP_2") (pintype "passive"))
      (node (ref "J9") (pin "12") (pinfunction "12_12") (pintype "bidirectional"))
      (node (ref "R14") (pin "1") (pinfunction "1_1") (pintype "bidirectional"))
      (node (ref "R18") (pin "2") (pinfunction "2_2") (pintype "passive"))
    )
    (net (code "12") (name "IA-") (class "Default")
      (node (ref "CT1") (pin "1") (pinfunction "1_1") (pintype "passive"))
      (node (ref "CT1-2") (pin "1") (pinfunction "SLEEVE_1") (pintype "passive"))
      (node (ref "J9") (pin "3") (pinfunction "3_3") (pintype "bidirectional"))
      (node (ref "JP1") (pin "2") (pinfunction "2_2") (pintype "passive"))
      (node (ref "R3") (pin "2") (pinfunction "2_2") (pintype "bidirectional"))
    )
    (net (code "13") (name "IA--2") (class "Default")
      (node (ref "CT4") (pin "1") (pinfunction "1_1") (pintype "passive"))
      (node (ref "CT4-2") (pin "1") (pinfunction "SLEEVE_1") (pintype "passive"))
      (node (ref "J9") (pin "13") (pinfunction "13_13") (pintype "bidirectional"))
      (node (ref "JP4") (pin "2") (pinfunction "2_2") (pintype "passive"))
      (node (ref "R14") (pin "2") (pinfunction "2_2") (pintype "bidirectional"))
    )
    (net (code "14") (name "IAN") (class "Default")
      (node (ref "C3") (pin "2") (pinfunction "2_2") (pintype "passive"))
      (node (ref "IC1") (pin "4") (pinfunction "I1N_4") (pintype "input"))
      (node (ref "R3") (pin "7") (pinfunction "7_7") (pintype "bidirectional"))
    )
    (net (code "15") (name "IAN-2") (class "Default")
      (node (ref "C18") (pin "2") (pinfunction "2_2") (pintype "passive"))
      (node (ref "IC2") (pin "4") (pinfunction "I1N_4") (pintype "input"))
      (node (ref "R14") (pin "7") (pinfunction "7_7") (pintype "bidirectional"))
    )
    (net (code "16") (name "IAP") (class "Default")
      (node (ref "C2") (pin "1") (pinfunction "1_1") (pintype "passive"))
      (node (ref "IC1") (pin "3") (pinfunction "I1P_3") (pintype "input"))
      (node (ref "R3") (pin "8") (pinfunction "8_8") (pintype "bidirectional"))
    )
    (net (code "17") (name "IAP-2") (class "Default")
      (node (ref "C17") (pin "1") (pinfunction "1_1") (pintype "passive"))
      (node (ref "IC2") (pin "3") (pinfunction "I1P_3") (pintype "input"))
      (node (ref "R14") (pin "8") (pinfunction "8_8") (pintype "bidirectional"))
    )
    (net (code "18") (name "IB+") (class "Default")
      (node (ref "CT2") (pin "2") (pinfunction "2_2") (pintype "passive"))
      (node (ref "CT2-2") (pin "2") (pinfunction "TIP_2") (pintype "passive"))
      (node (ref "J9") (pin "5") (pinfunction "5_5") (pintype "bidirectional"))
      (node (ref "R3") (pin "3") (pinfunction "3_3") (pintype "bidirectional"))
      (node (ref "R8") (pin "2") (pinfunction "2_2") (pintype "passive"))
    )
    (net (code "19") (name "IB+-2") (class "Default")
      (node (ref "CT5") (pin "2") (pinfunction "2_2") (pintype "passive"))
      (node (ref "CT5-2") (pin "2") (pinfunction "TIP_2") (pintype "passive"))
      (node (ref "J9") (pin "15") (pinfunction "15_15") (pintype "bidirectional"))
      (node (ref "R14") (pin "3") (pinfunction "3_3") (pintype "bidirectional"))
      (node (ref "R19") (pin "2") (pinfunction "2_2") (pintype "passive"))
    )
    (net (code "20") (name "IB-") (class "Default")
      (node (ref "CT2") (pin "1") (pinfunction "1_1") (pintype "passive"))
      (node (ref "CT2-2") (pin "1") (pinfunction "SLEEVE_1") (pintype "passive"))
      (node (ref "J9") (pin "6") (pinfunction "6_6") (pintype "bidirectional"))
      (node (ref "JP2") (pin "2") (pinfunction "2_2") (pintype "passive"))
      (node (ref "R3") (pin "4") (pinfunction "4_4") (pintype "bidirectional"))
    )
    (net (code "21") (name "IB--2") (class "Default")
      (node (ref "CT5") (pin "1") (pinfunction "1_1") (pintype "passive"))
      (node (ref "CT5-2") (pin "1") (pinfunction "SLEEVE_1") (pintype "passive"))
      (node (ref "J9") (pin "16") (pinfunction "16_16") (pintype "bidirectional"))
      (node (ref "JP5") (pin "2") (pinfunction "2_2") (pintype "passive"))
      (node (ref "R14") (pin "4") (pinfunction "4_4") (pintype "bidirectional"))
    )
    (net (code "22") (name "IBN") (class "Default")
      (node (ref "C5") (pin "2") (pinfunction "2_2") (pintype "passive"))
      (node (ref "IC1") (pin "6") (pinfunction "I2N_6") (pintype "input"))
      (node (ref "R3") (pin "5") (pinfunction "5_5") (pintype "bidirectional"))
    )
    (net (code "23") (name "IBN-2") (class "Default")
      (node (ref "C20") (pin "2") (pinfunction "2_2") (pintype "passive"))
      (node (ref "IC2") (pin "6") (pinfunction "I2N_6") (pintype "input"))
      (node (ref "R14") (pin "5") (pinfunction "5_5") (pintype "bidirectional"))
    )
    (net (code "24") (name "IBP") (class "Default")
      (node (ref "C4") (pin "1") (pinfunction "1_1") (pintype "passive"))
      (node (ref "IC1") (pin "5") (pinfunction "I2P_5") (pintype "input"))
      (node (ref "R3") (pin "6") (pinfunction "6_6") (pintype "bidirectional"))
    )
    (net (code "25") (name "IBP-2") (class "Default")
      (node (ref "C19") (pin "1") (pinfunction "1_1") (pintype "passive"))
      (node (ref "IC2") (pin "5") (pinfunction "I2P_5") (pintype "input"))
      (node (ref "R14") (pin "6") (pinfunction "6_6") (pintype "bidirectional"))
    )
    (net (code "26") (name "IC+") (class "Default")
      (node (ref "CT3") (pin "2") (pinfunction "2_2") (pintype "passive"))
      (node (ref "CT3-2") (pin "2") (pinfunction "TIP_2") (pintype "passive"))
      (node (ref "J9") (pin "8") (pinfunction "8_8") (pintype "bidirectional"))
      (node (ref "R4") (pin "2") (pinfunction "2_2") (pintype "passive"))
      (node (ref "R6") (pin "2") (pinfunction "2_2") (pintype "passive"))
    )
    (net (code "27") (name "IC+-2") (class "Default")
      (node (ref "CT6") (pin "2") (pinfunction "2_2") (pintype "passive"))
      (node (ref "CT6-2") (pin "2") (pinfunction "TIP_2") (pintype "passive"))
      (node (ref "J9") (pin "18") (pinfunction "18_18") (pintype "bidirectional"))
      (node (ref "R15") (pin "2") (pinfunction "2_2") (pintype "passive"))
      (node (ref "R17") (pin "2") (pinfunction "2_2") (pintype "passive"))
    )
    (net (code "28") (name "IC-") (class "Default")
      (node (ref "CT3") (pin "1") (pinfunction "1_1") (pintype "passive"))
      (node (ref "CT3-2") (pin "1") (pinfunction "SLEEVE_1") (pintype "passive"))
      (node (ref "J9") (pin "9") (pinfunction "9_9") (pintype "bidirectional"))
      (node (ref "JP3") (pin "2") (pinfunction "2_2") (pintype "passive"))
      (node (ref "R5") (pin "2") (pinfunction "2_2") (pintype "passive"))
    )
    (net (code "29") (name "IC--2") (class "Default")
      (node (ref "CT6") (pin "1") (pinfunction "1_1") (pintype "passive"))
      (node (ref "CT6-2") (pin "1") (pinfunction "SLEEVE_1") (pintype "passive"))
      (node (ref "J9") (pin "17") (pinfunction "17_17") (pintype "bidirectional"))
      (node (ref "JP6") (pin "2") (pinfunction "2_2") (pintype "passive"))
      (node (ref "R16") (pin "2") (pinfunction "2_2") (pintype "passive"))
    )
    (net (code "30") (name "ICN") (class "Default")
      (node (ref "C7") (pin "2") (pinfunction "2_2") (pintype "passive"))
      (node (ref "IC1") (pin "8") (pinfunction "I3N_8") (pintype "input"))
      (node (ref "R5") (pin "1") (pinfunction "1_1") (pintype "passive"))
    )
    (net (code "31") (name "ICN-2") (class "Default")
      (node (ref "C22") (pin "2") (pinfunction "2_2") (pintype "passive"))
      (node (ref "IC2") (pin "8") (pinfunction "I3N_8") (pintype "input"))
      (node (ref "R16") (pin "1") (pinfunction "1_1") (pintype "passive"))
    )
    (net (code "32") (name "ICP") (class "Default")
      (node (ref "C6") (pin "1") (pinfunction "1_1") (pintype "passive"))
      (node (ref "IC1") (pin "7") (pinfunction "I3P_7") (pintype "input"))
      (node (ref "R4") (pin "1") (pinfunction "1_1") (pintype "passive"))
    )
    (net (code "33") (name "ICP-2") (class "Default")
      (node (ref "C21") (pin "1") (pinfunction "1_1") (pintype "passive"))
      (node (ref "IC2") (pin "7") (pinfunction "I3P_7") (pintype "input"))
      (node (ref "R15") (pin "1") (pinfunction "1_1") (pintype "passive"))
    )
    (net (code "34") (name "IO0") (class "Default")
      (node (ref "U1") (pin "33") (pinfunction "IO0_33") (pintype "bidirectional"))
    )
    (net (code "35") (name "IO2") (class "Default")
      (node (ref "U1") (pin "34") (pinfunction "IO2_34") (pintype "bidirectional"))
    )
    (net (code "36") (name "IO12") (class "Default")
      (node (ref "J16") (pin "13") (pinfunction "13_13") (pintype "passive"))
      (node (ref "U1") (pin "13") (pinfunction "IO12_13") (pintype "bidirectional"))
    )
    (net (code "37") (name "IO13") (class "Default")
      (node (ref "J16") (pin "15") (pinfunction "15_15") (pintype "passive"))
      (node (ref "U1") (pin "15") (pinfunction "IO13_15") (pintype "bidirectional"))
    )
    (net (code "38") (name "IO14") (class "Default")
      (node (ref "J16") (pin "12") (pinfunction "12_12") (pintype "passive"))
      (node (ref "U1") (pin "12") (pinfunction "IO14_12") (pintype "bidirectional"))
    )
    (net (code "39") (name "IO15") (class "Default")
      (node (ref "U1") (pin "35") (pinfunction "IO15_35") (pintype "bidirectional"))
    )
    (net (code "40") (name "IO16") (class "Default")
      (node (ref "U1") (pin "31") (pinfunction "IO16_31") (pintype "bidirectional"))
    )
    (net (code "41") (name "IO17") (class "Default")
      (node (ref "U1") (pin "30") (pinfunction "IO17_30") (pintype "bidirectional"))
    )
    (net (code "42") (name "IO21") (class "Default")
      (node (ref "U1") (pin "25") (pinfunction "IO21_25") (pintype "bidirectional"))
    )
    (net (code "43") (name "IO22") (class "Default")
      (node (ref "U1") (pin "22") (pinfunction "IO22_22") (pintype "bidirectional"))
    )
    (net (code "44") (name "IO25") (class "Default")
      (node (ref "J16") (pin "9") (pinfunction "9_9") (pintype "passive"))
      (node (ref "U1") (pin "9") (pinfunction "IO25_9") (pintype "bidirectional"))
    )
    (net (code "45") (name "IO26") (class "Default")
      (node (ref "J16") (pin "10") (pinfunction "10_10") (pintype "passive"))
      (node (ref "U1") (pin "10") (pinfunction "IO26_10") (pintype "bidirectional"))
    )
    (net (code "46") (name "IO27") (class "Default")
      (node (ref "J16") (pin "11") (pinfunction "11_11") (pintype "passive"))
      (node (ref "U1") (pin "11") (pinfunction "IO27_11") (pintype "bidirectional"))
    )
    (net (code "47") (name "IO35") (class "Default")
      (node (ref "J16") (pin "6") (pinfunction "6_6") (pintype "passive"))
      (node (ref "U1") (pin "6") (pinfunction "IO35_6") (pintype "bidirectional"))
    )
    (net (code "48") (name "IRQ0") (class "Default")
      (node (ref "IC1") (pin "30") (pinfunction "IRQ0_30") (pintype "output"))
      (node (ref "IC2") (pin "30") (pinfunction "IRQ0_30") (pintype "output"))
      (node (ref "J16") (pin "7") (pinfunction "7_7") (pintype "passive"))
      (node (ref "U1") (pin "7") (pinfunction "IO32_7") (pintype "bidirectional"))
    )
    (net (code "49") (name "IRQ1") (class "Default")
      (node (ref "IC1") (pin "31") (pinfunction "IRQ1_31") (pintype "output"))
      (node (ref "IC2") (pin "31") (pinfunction "IRQ1_31") (pintype "output"))
      (node (ref "J16") (pin "8") (pinfunction "8_8") (pintype "passive"))
      (node (ref "U1") (pin "8") (pinfunction "IO33_8") (pintype "bidirectional"))
    )
    (net (code "50") (name "MISO") (class "Default")
      (node (ref "IC1") (pin "39") (pinfunction "SDO_39") (pintype "output"))
      (node (ref "IC2") (pin "39") (pinfunction "SDO_39") (pintype "output"))
      (node (ref "R13") (pin "2") (pinfunction "2_2") (pintype "bidirectional"))
      (node (ref "R2") (pin "2") (pinfunction "2_2") (pintype "bidirectional"))
      (node (ref "U1") (pin "27") (pinfunction "IO19_27") (pintype "bidirectional"))
    )
    (net (code "51") (name "MOSI") (class "Default")
      (node (ref "IC1") (pin "40") (pinfunction "SDI_40") (pintype "input"))
      (node (ref "IC2") (pin "40") (pinfunction "SDI_40") (pintype "input"))
      (node (ref "R13") (pin "1") (pinfunction "1_1") (pintype "bidirectional"))
      (node (ref "R2") (pin "1") (pinfunction "1_1") (pintype "bidirectional"))
      (node (ref "U1") (pin "21") (pinfunction "IO23_21") (pintype "bidirectional"))
    )
    (net (code "52") (name "Net-(BR1-~{1})") (class "Default")
      (node (ref "BR1") (pin "1") (pinfunction "~{1}_1") (pintype "bidirectional"))
      (node (ref "C33") (pin "+") (pinfunction "+_+") (pintype "passive"))
      (node (ref "C34") (pin "1") (pinfunction "1_1") (pintype "passive"))
      (node (ref "IC3") (pin "2") (pinfunction "VIN_2") (pintype "input"))
      (node (ref "IC3") (pin "3") (pinfunction "EN_3") (pintype "bidirectional"))
    )
    (net (code "53") (name "Net-(C8-Pad2)") (class "Default")
      (node (ref "C8") (pin "2") (pinfunction "2_2") (pintype "passive"))
      (node (ref "C9") (pin "2") (pinfunction "2_2") (pintype "passive"))
      (node (ref "IC1") (pin "42") (pinfunction "VDD18_42") (pintype "power_in"))
      (node (ref "IC1") (pin "43") (pinfunction "VDD18_43") (pintype "power_in"))
    )
    (net (code "54") (name "Net-(C23-Pad2)") (class "Default")
      (node (ref "C23") (pin "2") (pinfunction "2_2") (pintype "passive"))
      (node (ref "C24") (pin "2") (pinfunction "2_2") (pintype "passive"))
      (node (ref "IC2") (pin "42") (pinfunction "VDD18_42") (pintype "power_in"))
      (node (ref "IC2") (pin "43") (pinfunction "VDD18_43") (pintype "power_in"))
    )
    (net (code "55") (name "Net-(CF1-2-PadA)") (class "Default")
      (node (ref "CF1-2") (pin "A") (pinfunction "A_A") (pintype "passive"))
      (node (ref "R20") (pin "1") (pinfunction "1_1") (pintype "passive"))
    )
    (net (code "56") (name "Net-(CF1-PadA)") (class "Default")
      (node (ref "CF1") (pin "A") (pinfunction "A_A") (pintype "passive"))
      (node (ref "R9") (pin "1") (pinfunction "1_1") (pintype "passive"))
    )
    (net (code "57") (name "Net-(IC1-OSCI)") (class "Default")
      (node (ref "IC1") (pin "20") (pinfunction "OSCI_20") (pintype "input"))
      (node (ref "Y1") (pin "1") (pinfunction "1_1") (pintype "passive"))
    )
    (net (code "58") (name "Net-(IC1-OSCO)") (class "Default")
      (node (ref "IC1") (pin "21") (pinfunction "OSCO_21") (pintype "output"))
      (node (ref "Y1") (pin "3") (pinfunction "2_3") (pintype "passive"))
    )
    (net (code "59") (name "Net-(IC1-VREF)") (class "Default")
      (node (ref "C12") (pin "1") (pinfunction "1_1") (pintype "passive"))
      (node (ref "C13") (pin "1") (pinfunction "1_1") (pintype "passive"))
      (node (ref "IC1") (pin "11") (pinfunction "VREF_11") (pintype "bidirectional"))
    )
    (net (code "60") (name "Net-(IC1-~{RESET})") (class "Default")
      (node (ref "C1") (pin "2") (pinfunction "2_2") (pintype "passive"))
      (node (ref "IC1") (pin "41") (pinfunction "~{RESET}_41") (pintype "input"))
      (node (ref "R1") (pin "2") (pinfunction "2_2") (pintype "passive"))
    )
    (net (code "61") (name "Net-(IC2-OSCI)") (class "Default")
      (node (ref "IC2") (pin "20") (pinfunction "OSCI_20") (pintype "input"))
      (node (ref "Y2") (pin "1") (pinfunction "1_1") (pintype "passive"))
    )
    (net (code "62") (name "Net-(IC2-OSCO)") (class "Default")
      (node (ref "IC2") (pin "21") (pinfunction "OSCO_21") (pintype "output"))
      (node (ref "Y2") (pin "3") (pinfunction "2_3") (pintype "passive"))
    )
    (net (code "63") (name "Net-(IC2-VREF)") (class "Default")
      (node (ref "C27") (pin "1") (pinfunction "1_1") (pintype "passive"))
      (node (ref "C28") (pin "1") (pinfunction "1_1") (pintype "passive"))
      (node (ref "IC2") (pin "11") (pinfunction "VREF_11") (pintype "bidirectional"))
    )
    (net (code "64") (name "Net-(IC2-~{RESET})") (class "Default")
      (node (ref "C16") (pin "2") (pinfunction "2_2") (pintype "passive"))
      (node (ref "IC2") (pin "41") (pinfunction "~{RESET}_41") (pintype "input"))
      (node (ref "R12") (pin "2") (pinfunction "2_2") (pintype "passive"))
    )
    (net (code "65") (name "Net-(IC3-BOOT)") (class "Default")
      (node (ref "C31") (pin "1") (pinfunction "1_1") (pintype "passive"))
      (node (ref "IC3") (pin "1") (pinfunction "BOOT_1") (pintype "bidirectional"))
    )
    (net (code "66") (name "Net-(IC3-FB)") (class "Default")
      (node (ref "C32") (pin "2") (pinfunction "2_2") (pintype "passive"))
      (node (ref "IC3") (pin "5") (pinfunction "FB_5") (pintype "bidirectional"))
      (node (ref "R22") (pin "1") (pinfunction "1_1") (pintype "passive"))
      (node (ref "R23") (pin "2") (pinfunction "2_2") (pintype "passive"))
    )
    (net (code "67") (name "Net-(IC3-RT{slash}SYNC)") (class "Default")
      (node (ref "IC3") (pin "4") (pinfunction "RT/SYNC_4") (pintype "bidirectional"))
      (node (ref "R21") (pin "2") (pinfunction "2_2") (pintype "passive"))
    )
    (net (code "68") (name "Net-(IC3-SS)") (class "Default")
      (node (ref "C35") (pin "1") (pinfunction "1_1") (pintype "passive"))
      (node (ref "IC3") (pin "6") (pinfunction "SS_6") (pintype "bidirectional"))
    )
    (net (code "69") (name "Net-(IC3-SW)") (class "Default")
      (node (ref "C31") (pin "2") (pinfunction "2_2") (pintype "passive"))
      (node (ref "D1") (pin "C") (pinfunction "C_C") (pintype "passive"))
      (node (ref "IC3") (pin "8") (pinfunction "SW_8") (pintype "bidirectional"))
      (node (ref "L1") (pin "1") (pinfunction "1_1") (pintype "power_in"))
    )
    (net (code "70") (name "Net-(JP1-Pad1)") (class "Default")
      (node (ref "JP1") (pin "1") (pinfunction "1_1") (pintype "passive"))
      (node (ref "R7") (pin "1") (pinfunction "1_1") (pintype "passive"))
    )
    (net (code "71") (name "Net-(JP2-Pad1)") (class "Default")
      (node (ref "JP2") (pin "1") (pinfunction "1_1") (pintype "passive"))
      (node (ref "R8") (pin "1") (pinfunction "1_1") (pintype "passive"))
    )
    (net (code "72") (name "Net-(JP3-Pad1)") (class "Default")
      (node (ref "JP3") (pin "1") (pinfunction "1_1") (pintype "passive"))
      (node (ref "R6") (pin "1") (pinfunction "1_1") (pintype "passive"))
    )
    (net (code "73") (name "Net-(JP4-Pad1)") (class "Default")
      (node (ref "JP4") (pin "1") (pinfunction "1_1") (pintype "passive"))
      (node (ref "R18") (pin "1") (pinfunction "1_1") (pintype "passive"))
    )
    (net (code "74") (name "Net-(JP5-Pad1)") (class "Default")
      (node (ref "JP5") (pin "1") (pinfunction "1_1") (pintype "passive"))
      (node (ref "R19") (pin "1") (pinfunction "1_1") (pintype "passive"))
    )
    (net (code "75") (name "Net-(JP6-Pad1)") (class "Default")
      (node (ref "JP6") (pin "1") (pinfunction "1_1") (pintype "passive"))
      (node (ref "R17") (pin "1") (pinfunction "1_1") (pintype "passive"))
    )
    (net (code "76") (name "Net-(PWR-PadA)") (class "Default")
      (node (ref "PWR") (pin "A") (pinfunction "A_A") (pintype "passive"))
      (node (ref "R10") (pin "1") (pinfunction "1_1") (pintype "passive"))
    )
    (net (code "77") (name "Net-(U1-CMD)") (class "Default")
      (node (ref "J16") (pin "18") (pinfunction "18_18") (pintype "passive"))
      (node (ref "U1") (pin "18") (pinfunction "CMD_18") (pintype "bidirectional"))
    )
    (net (code "78") (name "Net-(U1-EN)") (class "Default")
      (node (ref "J16") (pin "2") (pinfunction "2_2") (pintype "passive"))
      (node (ref "U1") (pin "2") (pinfunction "EN_2") (pintype "input"))
    )
    (net (code "79") (name "Net-(U1-EXT_5V)") (class "Default")
      (node (ref "J16") (pin "19") (pinfunction "19_19") (pintype "passive"))
      (node (ref "U1") (pin "19") (pinfunction "EXT_5V_19") (pintype "power_in"))
    )
    (net (code "80") (name "Net-(U1-SD2)") (class "Default")
      (node (ref "J16") (pin "16") (pinfunction "16_16") (pintype "passive"))
      (node (ref "U1") (pin "16") (pinfunction "SD2_16") (pintype "bidirectional"))
    )
    (net (code "81") (name "Net-(U1-SD3)") (class "Default")
      (node (ref "J16") (pin "17") (pinfunction "17_17") (pintype "passive"))
      (node (ref "U1") (pin "17") (pinfunction "SD3_17") (pintype "bidirectional"))
    )
    (net (code "82") (name "Net-(U1-SENSOR_VN)") (class "Default")
      (node (ref "J16") (pin "4") (pinfunction "4_4") (pintype "passive"))
      (node (ref "U1") (pin "4") (pinfunction "SENSOR_VN_4") (pintype "input"))
    )
    (net (code "83") (name "Net-(U1-SENSOR_VP)") (class "Default")
      (node (ref "J16") (pin "3") (pinfunction "3_3") (pintype "passive"))
      (node (ref "U1") (pin "3") (pinfunction "SENSOR_VP_3") (pintype "input"))
    )
    (net (code "84") (name "SCLK") (class "Default")
      (node (ref "IC1") (pin "38") (pinfunction "SCLK_38") (pintype "input"))
      (node (ref "IC2") (pin "38") (pinfunction "SCLK_38") (pintype "input"))
      (node (ref "R13") (pin "3") (pinfunction "3_3") (pintype "bidirectional"))
      (node (ref "R2") (pin "3") (pinfunction "3_3") (pintype "bidirectional"))
      (node (ref "U1") (pin "28") (pinfunction "IO18_28") (pintype "bidirectional"))
    )
    (net (code "85") (name "VA+") (class "Default")
      (node (ref "BR1") (pin "4") (pinfunction "-_4") (pintype "bidirectional"))
      (node (ref "J4") (pin "1A") (pinfunction "1_1A") (pintype "passive"))
      (node (ref "J4") (pin "1B") (pinfunction "1_1B") (pintype "passive"))
      (node (ref "J8") (pin "1") (pinfunction "1_1") (pintype "passive"))
      (node (ref "JP12") (pin "2") (pinfunction "2_2") (pintype "passive"))
      (node (ref "R26") (pin "2") (pinfunction "2_2") (pintype "passive"))
    )
    (net (code "86") (name "VA-") (class "Default")
      (node (ref "BR1") (pin "3") (pinfunction "+_3") (pintype "bidirectional"))
      (node (ref "J4") (pin "2") (pinfunction "2_2") (pintype "passive"))
      (node (ref "J6") (pin "1") (pinfunction "1_1") (pintype "passive"))
      (node (ref "JP13") (pin "2") (pinfunction "2_2") (pintype "passive"))
      (node (ref "R34") (pin "2") (pinfunction "2_2") (pintype "passive"))
    )
    (net (code "87") (name "VA2+") (class "Default")
      (node (ref "J3") (pin "2") (pinfunction "2_2") (pintype "passive"))
      (node (ref "JP12") (pin "1") (pinfunction "1_1") (pintype "passive"))
      (node (ref "R28") (pin "2") (pinfunction "2_2") (pintype "passive"))
    )
    (net (code "88") (name "VA2-") (class "Default")
      (node (ref "J3") (pin "1") (pinfunction "1_1") (pintype "passive"))
      (node (ref "JP13") (pin "1") (pinfunction "1_1") (pintype "passive"))
      (node (ref "R32") (pin "2") (pinfunction "2_2") (pintype "passive"))
    )
    (net (code "89") (name "VAN") (class "Default")
      (node (ref "C15") (pin "1") (pinfunction "1_1") (pintype "passive"))
      (node (ref "IC1") (pin "14") (pinfunction "V1N_14") (pintype "input"))
      (node (ref "IC1") (pin "16") (pinfunction "V2N_16") (pintype "input"))
      (node (ref "IC1") (pin "18") (pinfunction "V3N_18") (pintype "input"))
      (node (ref "R11") (pin "6") (pinfunction "6_6") (pintype "bidirectional"))
      (node (ref "R24") (pin "7") (pinfunction "7_7") (pintype "bidirectional"))
      (node (ref "R34") (pin "1") (pinfunction "1_1") (pintype "passive"))
    )
    (net (code "90") (name "VAN2") (class "Default")
      (node (ref "C30") (pin "1") (pinfunction "1_1") (pintype "passive"))
      (node (ref "IC2") (pin "14") (pinfunction "V1N_14") (pintype "input"))
      (node (ref "IC2") (pin "16") (pinfunction "V2N_16") (pintype "input"))
      (node (ref "IC2") (pin "18") (pinfunction "V3N_18") (pintype "input"))
      (node (ref "R11") (pin "5") (pinfunction "5_5") (pintype "bidirectional"))
      (node (ref "R24") (pin "8") (pinfunction "8_8") (pintype "bidirectional"))
      (node (ref "R32") (pin "1") (pinfunction "1_1") (pintype "passive"))
    )
    (net (code "91") (name "VAP") (class "Default")
      (node (ref "C14") (pin "1") (pinfunction "1_1") (pintype "passive"))
      (node (ref "IC1") (pin "13") (pinfunction "V1P_13") (pintype "input"))
      (node (ref "IC1") (pin "15") (pinfunction "V2P_15") (pintype "input"))
      (node (ref "IC1") (pin "17") (pinfunction "V3P_17") (pintype "input"))
      (node (ref "R11") (pin "7") (pinfunction "7_7") (pintype "bidirectional"))
      (node (ref "R24") (pin "6") (pinfunction "6_6") (pintype "bidirectional"))
      (node (ref "R26") (pin "1") (pinfunction "1_1") (pintype "passive"))
    )
    (net (code "92") (name "VAP2") (class "Default")
      (node (ref "C29") (pin "1") (pinfunction "1_1") (pintype "passive"))
      (node (ref "IC2") (pin "13") (pinfunction "V1P_13") (pintype "input"))
      (node (ref "IC2") (pin "15") (pinfunction "V2P_15") (pintype "input"))
      (node (ref "IC2") (pin "17") (pinfunction "V3P_17") (pintype "input"))
      (node (ref "R11") (pin "8") (pinfunction "8_8") (pintype "bidirectional"))
      (node (ref "R24") (pin "5") (pinfunction "5_5") (pintype "bidirectional"))
      (node (ref "R28") (pin "1") (pinfunction "1_1") (pintype "passive"))
    )
    (net (code "93") (name "VDD") (class "Default")
      (node (ref "C10") (pin "2") (pinfunction "2_2") (pintype "passive"))
      (node (ref "C11") (pin "2") (pinfunction "2_2") (pintype "passive"))
      (node (ref "C25") (pin "2") (pinfunction "2_2") (pintype "passive"))
      (node (ref "C26") (pin "2") (pinfunction "2_2") (pintype "passive"))
      (node (ref "C32") (pin "1") (pinfunction "1_1") (pintype "passive"))
      (node (ref "C36") (pin "1") (pinfunction "1_1") (pintype "passive"))
      (node (ref "IC1") (pin "1") (pinfunction "AVDD_1") (pintype "power_in"))
      (node (ref "IC1") (pin "33") (pinfunction "PM0_33") (pintype "input"))
      (node (ref "IC1") (pin "34") (pinfunction "PM1_34") (pintype "input"))
      (node (ref "IC1") (pin "48") (pinfunction "DVDD_48") (pintype "power_in"))
      (node (ref "IC2") (pin "1") (pinfunction "AVDD_1") (pintype "power_in"))
      (node (ref "IC2") (pin "33") (pinfunction "PM0_33") (pintype "input"))
      (node (ref "IC2") (pin "34") (pinfunction "PM1_34") (pintype "input"))
      (node (ref "IC2") (pin "48") (pinfunction "DVDD_48") (pintype "power_in"))
      (node (ref "J16") (pin "1") (pinfunction "1_1") (pintype "passive"))
      (node (ref "L1") (pin "2") (pinfunction "2_2") (pintype "power_in"))
      (node (ref "R1") (pin "1") (pinfunction "1_1") (pintype "passive"))
      (node (ref "R10") (pin "2") (pinfunction "2_2") (pintype "passive"))
      (node (ref "R12") (pin "1") (pinfunction "1_1") (pintype "passive"))
      (node (ref "R13") (pin "5") (pinfunction "5_5") (pintype "bidirectional"))
      (node (ref "R13") (pin "6") (pinfunction "6_6") (pintype "bidirectional"))
      (node (ref "R13") (pin "7") (pinfunction "7_7") (pintype "bidirectional"))
      (node (ref "R13") (pin "8") (pinfunction "8_8") (pintype "bidirectional"))
      (node (ref "R2") (pin "5") (pinfunction "5_5") (pintype "bidirectional"))
      (node (ref "R2") (pin "6") (pinfunction "6_6") (pintype "bidirectional"))
      (node (ref "R2") (pin "7") (pinfunction "7_7") (pintype "bidirectional"))
      (node (ref "R2") (pin "8") (pinfunction "8_8") (pintype "bidirectional"))
      (node (ref "R22") (pin "2") (pinfunction "2_2") (pintype "passive"))
      (node (ref "R24") (pin "1") (pinfunction "1_1") (pintype "bidirectional"))
      (node (ref "R24") (pin "2") (pinfunction "2_2") (pintype "bidirectional"))
      (node (ref "R24") (pin "3") (pinfunction "3_3") (pintype "bidirectional"))
      (node (ref "R24") (pin "4") (pinfunction "4_4") (pintype "bidirectional"))
      (node (ref "U1") (pin "1") (pinfunction "3V3_1") (pintype "power_in"))
    )
    (net (code "94") (name "WARN") (class "Default")
      (node (ref "IC1") (pin "29") (pinfunction "WARNOUT_29") (pintype "output"))
      (node (ref "IC2") (pin "29") (pinfunction "WARNOUT_29") (pintype "output"))
      (node (ref "J16") (pin "5") (pinfunction "5_5") (pintype "passive"))
      (node (ref "U1") (pin "5") (pinfunction "IO34_5") (pintype "bidirectional"))
    )
    (net (code "95") (name "ZX0") (class "Default")
      (node (ref "IC1") (pin "22") (pinfunction "ZX0_22") (pintype "output"))
      (node (ref "ZX0") (pin "1") (pinfunction "P_1") (pintype "passive"))
    )
    (net (code "96") (name "ZX0-2") (class "Default")
      (node (ref "IC2") (pin "22") (pinfunction "ZX0_22") (pintype "output"))
      (node (ref "ZX0-2") (pin "1") (pinfunction "P_1") (pintype "passive"))
    )
    (net (code "97") (name "ZX1") (class "Default")
      (node (ref "IC1") (pin "23") (pinfunction "ZX1_23") (pintype "output"))
      (node (ref "ZX1") (pin "1") (pinfunction "P_1") (pintype "passive"))
    )
    (net (code "98") (name "ZX1-2") (class "Default")
      (node (ref "IC2") (pin "23") (pinfunction "ZX1_23") (pintype "output"))
      (node (ref "ZX1-2") (pin "1") (pinfunction "P_1") (pintype "passive"))
    )
    (net (code "99") (name "ZX2") (class "Default")
      (node (ref "IC1") (pin "24") (pinfunction "ZX2_24") (pintype "output"))
      (node (ref "ZX2") (pin "1") (pinfunction "P_1") (pintype "passive"))
    )
    (net (code "100") (name "ZX2-2") (class "Default")
      (node (ref "IC2") (pin "24") (pinfunction "ZX2_24") (pintype "output"))
      (node (ref "ZX2-2") (pin "1") (pinfunction "P_1") (pintype "passive"))
    )
    (net (code "101") (name "unconnected-(CT1-2-RING-Pad3)") (class "Default")
      (node (ref "CT1-2") (pin "3") (pinfunction "RING_3") (pintype "passive"))
    )
    (net (code "102") (name "unconnected-(CT1-2-TIP_SWITCH-Pad10)") (class "Default")
      (node (ref "CT1-2") (pin "10") (pinfunction "TIP_SWITCH_10") (pintype "passive"))
    )
    (net (code "103") (name "unconnected-(CT2-2-RING-Pad3)") (class "Default")
      (node (ref "CT2-2") (pin "3") (pinfunction "RING_3") (pintype "passive"))
    )
    (net (code "104") (name "unconnected-(CT2-2-TIP_SWITCH-Pad10)") (class "Default")
      (node (ref "CT2-2") (pin "10") (pinfunction "TIP_SWITCH_10") (pintype "passive"))
    )
    (net (code "105") (name "unconnected-(CT3-2-RING-Pad3)") (class "Default")
      (node (ref "CT3-2") (pin "3") (pinfunction "RING_3") (pintype "passive"))
    )
    (net (code "106") (name "unconnected-(CT3-2-TIP_SWITCH-Pad10)") (class "Default")
      (node (ref "CT3-2") (pin "10") (pinfunction "TIP_SWITCH_10") (pintype "passive"))
    )
    (net (code "107") (name "unconnected-(CT4-2-RING-Pad3)") (class "Default")
      (node (ref "CT4-2") (pin "3") (pinfunction "RING_3") (pintype "passive"))
    )
    (net (code "108") (name "unconnected-(CT4-2-TIP_SWITCH-Pad10)") (class "Default")
      (node (ref "CT4-2") (pin "10") (pinfunction "TIP_SWITCH_10") (pintype "passive"))
    )
    (net (code "109") (name "unconnected-(CT5-2-RING-Pad3)") (class "Default")
      (node (ref "CT5-2") (pin "3") (pinfunction "RING_3") (pintype "passive"))
    )
    (net (code "110") (name "unconnected-(CT5-2-TIP_SWITCH-Pad10)") (class "Default")
      (node (ref "CT5-2") (pin "10") (pinfunction "TIP_SWITCH_10") (pintype "passive"))
    )
    (net (code "111") (name "unconnected-(CT6-2-RING-Pad3)") (class "Default")
      (node (ref "CT6-2") (pin "3") (pinfunction "RING_3") (pintype "passive"))
    )
    (net (code "112") (name "unconnected-(CT6-2-TIP_SWITCH-Pad10)") (class "Default")
      (node (ref "CT6-2") (pin "10") (pinfunction "TIP_SWITCH_10") (pintype "passive"))
    )
    (net (code "113") (name "unconnected-(IC1-I4N-Pad10)") (class "Default")
      (node (ref "IC1") (pin "10") (pinfunction "I4N_10") (pintype "input"))
    )
    (net (code "114") (name "unconnected-(IC1-I4P-Pad9)") (class "Default")
      (node (ref "IC1") (pin "9") (pinfunction "I4P_9") (pintype "input"))
    )
    (net (code "115") (name "unconnected-(IC1-NC-Pad35)") (class "Default")
      (node (ref "IC1") (pin "35") (pinfunction "NC_35") (pintype "no_connect"))
    )
    (net (code "116") (name "unconnected-(IC1-NC-Pad45)") (class "Default")
      (node (ref "IC1") (pin "45") (pinfunction "NC_45") (pintype "no_connect"))
    )
    (net (code "117") (name "unconnected-(IC1-NC-Pad46)") (class "Default")
      (node (ref "IC1") (pin "46") (pinfunction "NC_46") (pintype "no_connect"))
    )
    (net (code "118") (name "unconnected-(IC2-I4N-Pad10)") (class "Default")
      (node (ref "IC2") (pin "10") (pinfunction "I4N_10") (pintype "input"))
    )
    (net (code "119") (name "unconnected-(IC2-I4P-Pad9)") (class "Default")
      (node (ref "IC2") (pin "9") (pinfunction "I4P_9") (pintype "input"))
    )
    (net (code "120") (name "unconnected-(IC2-NC-Pad35)") (class "Default")
      (node (ref "IC2") (pin "35") (pinfunction "NC_35") (pintype "no_connect"))
    )
    (net (code "121") (name "unconnected-(IC2-NC-Pad45)") (class "Default")
      (node (ref "IC2") (pin "45") (pinfunction "NC_45") (pintype "no_connect"))
    )
    (net (code "122") (name "unconnected-(IC2-NC-Pad46)") (class "Default")
      (node (ref "IC2") (pin "46") (pinfunction "NC_46") (pintype "no_connect"))
    )
    (net (code "123") (name "unconnected-(J4-Pad3)") (class "Default")
      (node (ref "J4") (pin "3") (pinfunction "3_3") (pintype "passive"))
    )
    (net (code "124") (name "unconnected-(J5-Pad1)") (class "Default")
      (node (ref "J5") (pin "1") (pinfunction "1_1") (pintype "passive"))
    )
    (net (code "125") (name "unconnected-(U1-CLK-Pad38)") (class "Default")
      (node (ref "U1") (pin "38") (pinfunction "CLK_38") (pintype "input"))
    )
    (net (code "126") (name "unconnected-(U1-RXD0-Pad24)") (class "Default")
      (node (ref "U1") (pin "24") (pinfunction "RXD0_24") (pintype "input"))
    )
    (net (code "127") (name "unconnected-(U1-SD0-Pad37)") (class "Default")
      (node (ref "U1") (pin "37") (pinfunction "SD0_37") (pintype "bidirectional"))
    )
    (net (code "128") (name "unconnected-(U1-SD1-Pad36)") (class "Default")
      (node (ref "U1") (pin "36") (pinfunction "SD1_36") (pintype "bidirectional"))
    )
    (net (code "129") (name "unconnected-(U1-TXD0-Pad23)") (class "Default")
      (node (ref "U1") (pin "23") (pinfunction "TXD0_23") (pintype "output"))
    )
    (net (code "130") (name "~{CS-2}") (class "Default")
      (node (ref "IC2") (pin "37") (pinfunction "~{CS}_37") (pintype "input"))
      (node (ref "R13") (pin "4") (pinfunction "4_4") (pintype "bidirectional"))
      (node (ref "U1") (pin "32") (pinfunction "IO4_32") (pintype "bidirectional"))
    )
    (net (code "131") (name "~{CS}") (class "Default")
      (node (ref "IC1") (pin "37") (pinfunction "~{CS}_37") (pintype "input"))
      (node (ref "R2") (pin "4") (pinfunction "4_4") (pintype "bidirectional"))
      (node (ref "U1") (pin "29") (pinfunction "IO5_29") (pintype "bidirectional"))
    )
  )
)
